# PI_CAN_Interface_v3.net
KiCad netlist of a schematic drawn in Altium Designer
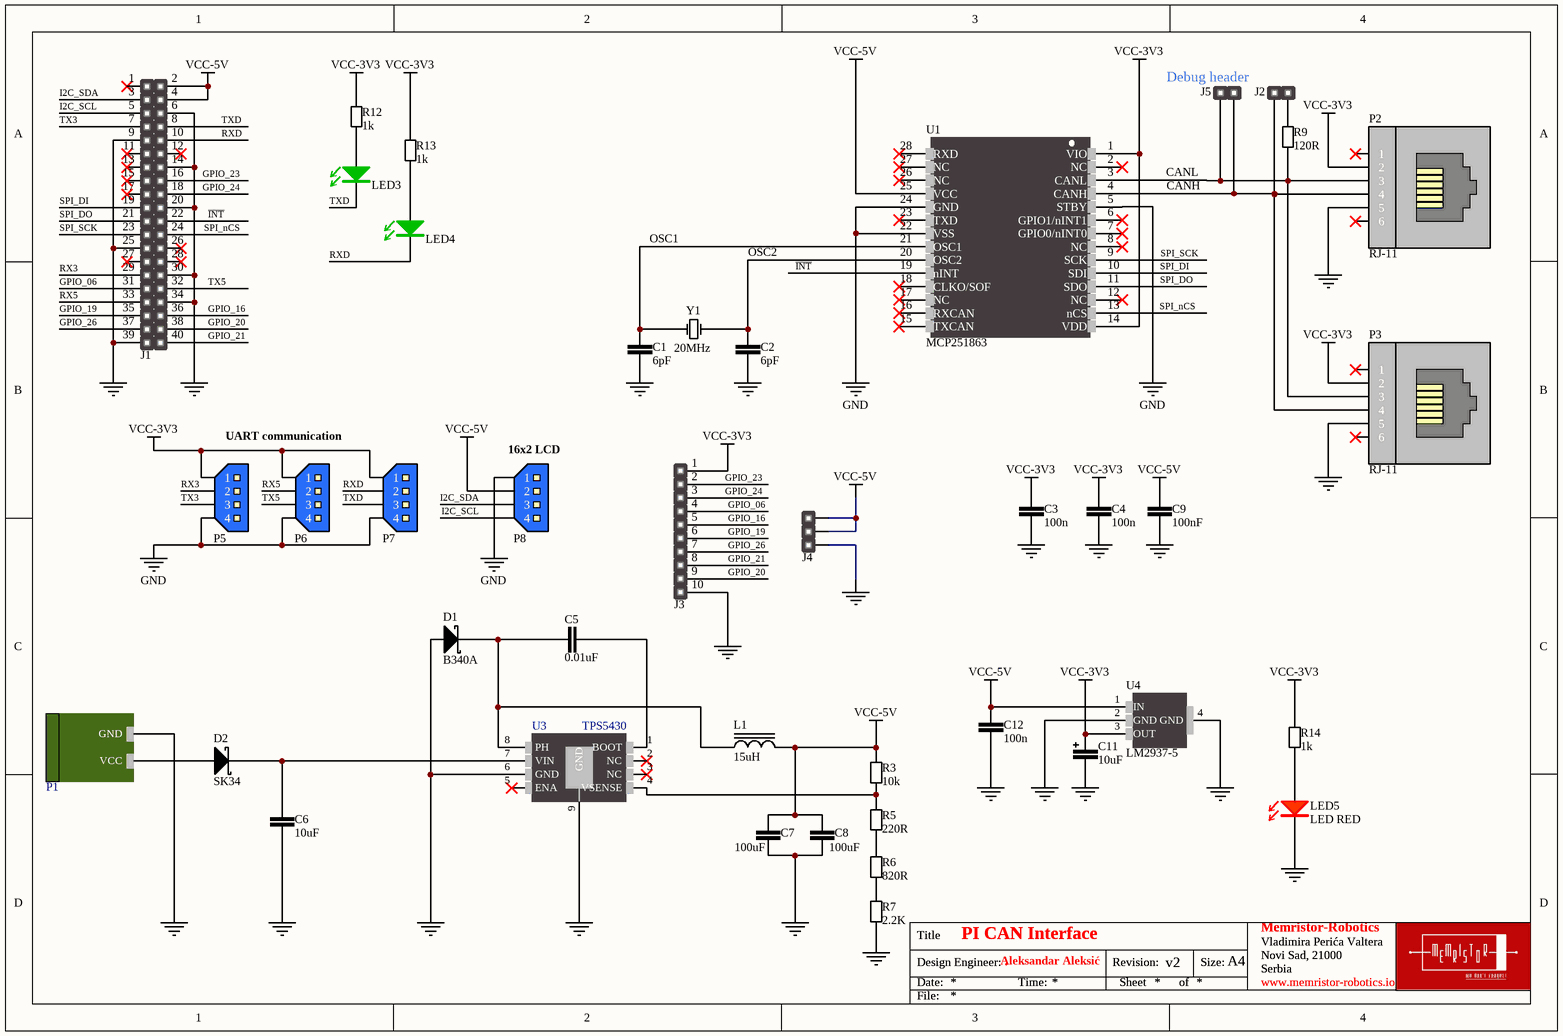
[diagram p0: PI_CAN_Interface_v3.SchDoc]

(export (version "E")
  (design (tool "Eeschema 10.0.6"))
  (components
    (comp (ref "C1")
      (value "6pF")
      (footprint "CER_0603")
      (description "CAP CER 20p 0805")
      (libsource (lib "Capacitors") (part "00002200"))
    )
    (comp (ref "C2")
      (value "6pF")
      (footprint "CER_0603")
      (description "CAP CER 20p 0805")
      (libsource (lib "Capacitors") (part "00002200"))
    )
    (comp (ref "C3")
      (value "100n")
      (footprint "CER_0603")
      (description "CAP CER 100n 10V X5R 10% 0603")
      (libsource (lib "Capacitors") (part "06032105"))
    )
    (comp (ref "C4")
      (value "100n")
      (footprint "CER_0603")
      (description "CAP CER 100n 10V X5R 10% 0603")
      (libsource (lib "Capacitors") (part "06032105"))
    )
    (comp (ref "C5")
      (value "0.01uF")
      (footprint "CER_0603")
      (description "CAP CER 100n 10V X5R 10% 0603")
      (libsource (lib "Capacitors") (part "06032105"))
    )
    (comp (ref "C6")
      (value "10uF")
      (footprint "CER_1210")
      (description "CAP CER 2.2u X7R 100V 20% 1210")
      (libsource (lib "Capacitors") (part "00002225"))
    )
    (comp (ref "C7")
      (value "100uF")
      (footprint "CER_1210")
      (description "CAP CER 100u X5R 6.3V 10% 1210")
      (libsource (lib "Capacitors") (part "00002108"))
    )
    (comp (ref "C8")
      (value "100uF")
      (footprint "CER_1210")
      (description "CAP CER 100u X5R 6.3V 10% 1210")
      (libsource (lib "Capacitors") (part "00002108"))
    )
    (comp (ref "C9")
      (value "100nF")
      (footprint "CER_0805")
      (description "CAP CER 100n 50V X7R 10% 0805")
      (libsource (lib "Capacitors") (part "00002105"))
    )
    (comp (ref "C11")
      (value "10uF")
      (footprint "Capacitors:TANT_1210")
      (description "CAP TANT 10u")
      (libsource (lib "Capacitors") (part "00001106"))
    )
    (comp (ref "C12")
      (value "100n")
      (footprint "CER_0603")
      (description "CAP CER 100n 10V X5R 10% 0603")
      (libsource (lib "Capacitors") (part "06032105"))
    )
    (comp (ref "D1")
      (value "B340A")
      (footprint "DO214AC")
      (description "DIODE SCHOTTKY 60V 3A DO214AC")
      (fields (field (name "MANUFACTURER") "Vishay Semiconductor Diodes Division"))
      (libsource (lib "Discrete_Semiconductor") (part "B360B"))
    )
    (comp (ref "D2")
      (value "SK34")
      (footprint "DO214AC")
      (description "DIODE SCHOTTKY 40V 3A DO214AC")
      (fields (field (name "MANUFACTURER") "Vishay Semiconductor Diodes Division"))
      (libsource (lib "Discrete_Semiconductor") (part "SK34"))
    )
    (comp (ref "J1")
      (value "00000005")
      (footprint "HM2X20")
      (libsource (lib "Electro_Mechanical") (part "00000005"))
    )
    (comp (ref "J2")
      (value "*")
      (footprint "Electro_Mechanical:HM1x2")
      (libsource (lib "Electro_Mechanical") (part "00000003"))
    )
    (comp (ref "J3")
      (value "00000006")
      (footprint "HM1X10")
      (libsource (lib "Electro_Mechanical") (part "00000006"))
    )
    (comp (ref "J4")
      (value "*")
      (footprint "HM1X3")
      (libsource (lib "Electro_Mechanical") (part "HEADER_1x3"))
    )
    (comp (ref "J5")
      (value "*")
      (footprint "HM1x2")
      (libsource (lib "Electro_Mechanical") (part "HEADER_1x2"))
    )
    (comp (ref "L1")
      (value "15uH")
      (footprint "INDUCTOR_SS1260-103MLD")
      (description "FIXED IND 10uH 3A")
      (fields
        (field (name "MANUFACTURER") "Coilcraft")
        (field (name "MANUFACTURER PART NUMBER") "XAL7030-103MEB")
      )
      (libsource (lib "Discrete_Semiconductor") (part "IND_10uH"))
    )
    (comp (ref "LED3")
      (value "LED GREEN")
      (footprint "LED_GREEN_0805")
      (description "LED GREEN CLEAR 0805 SMD")
      (fields
        (field (name "MANUFACTURER") "Kingbright")
        (field (name "MANUFACTURER PART NUMBER") "APT2012SGC")
      )
      (libsource (lib "Discrete_Semiconductor") (part "LED_GREEN 0805"))
    )
    (comp (ref "LED4")
      (value "LED GREEN")
      (footprint "LED_GREEN_0805")
      (description "LED GREEN CLEAR 0805 SMD")
      (fields
        (field (name "MANUFACTURER") "Kingbright")
        (field (name "MANUFACTURER PART NUMBER") "APT2012SGC")
      )
      (libsource (lib "Discrete_Semiconductor") (part "LED_GREEN 0805"))
    )
    (comp (ref "LED5")
      (value "LED RED")
      (footprint "LED_RED_0805")
      (description "LED RED 0805")
      (fields
        (field (name "MANUFACTURER") "BRIGHT LED ELECTRONICS")
        (field (name "MANUFACTURER PART NUMBER") "BL-HUB35A-AV-TRB")
      )
      (libsource (lib "Discrete_Semiconductor") (part "LED_RED_0805"))
    )
    (comp (ref "P1")
      (value "*")
      (footprint "PWR_Con")
      (libsource (lib "Electro_Mechanical") (part "00000002"))
    )
    (comp (ref "P2")
      (value "RJ-11")
      (footprint "RJ11-6N-B")
      (libsource (lib "Electro_Mechanical") (part "00000001"))
    )
    (comp (ref "P3")
      (value "RJ-11")
      (footprint "RJ11-6N-B")
      (libsource (lib "Electro_Mechanical") (part "00000001"))
    )
    (comp (ref "P5")
      (value "TE CONNECTIVITY_4PIN_MALE")
      (footprint "TE CONNECTIVITY_4PIN_MALE")
      (description "BLUE_4PIN_CONECTOR")
      (fields (field (name "MANUFACTURER") "TE CONNECTIVITY / AMP"))
      (libsource (lib "Electro_Mechanical") (part "TE CONNECTIVITY_4PIN_MALE"))
    )
    (comp (ref "P6")
      (value "TE CONNECTIVITY_4PIN_MALE")
      (footprint "TE CONNECTIVITY_4PIN_MALE")
      (description "BLUE_4PIN_CONECTOR")
      (fields (field (name "MANUFACTURER") "TE CONNECTIVITY / AMP"))
      (libsource (lib "Electro_Mechanical") (part "TE CONNECTIVITY_4PIN_MALE"))
    )
    (comp (ref "P7")
      (value "TE CONNECTIVITY_4PIN_MALE")
      (footprint "TE CONNECTIVITY_4PIN_MALE")
      (description "BLUE_4PIN_CONECTOR")
      (fields (field (name "MANUFACTURER") "TE CONNECTIVITY / AMP"))
      (libsource (lib "Electro_Mechanical") (part "TE CONNECTIVITY_4PIN_MALE"))
    )
    (comp (ref "P8")
      (value "TE CONNECTIVITY_4PIN_MALE")
      (footprint "TE CONNECTIVITY_4PIN_MALE")
      (description "BLUE_4PIN_CONECTOR")
      (fields (field (name "MANUFACTURER") "TE CONNECTIVITY / AMP"))
      (libsource (lib "Electro_Mechanical") (part "TE CONNECTIVITY_4PIN_MALE"))
    )
    (comp (ref "R3")
      (value "10k")
      (footprint "RESC2013X38N-0805-NOOVERLAY")
      (description "RES SMD 51 kOhm 1/8W 0805")
      (fields (field (name "POWER") "0.125W, 1/8W"))
      (libsource (lib "Resistors") (part "00005102"))
    )
    (comp (ref "R5")
      (value "220R")
      (footprint "RESC2013X38N-0805-NOOVERLAY")
      (description "RES SMD 9.1 kOhm 1/8W 0805")
      (fields (field (name "POWER") "0.125W, 1/8W"))
      (libsource (lib "Resistors") (part "00009101"))
    )
    (comp (ref "R6")
      (value "820R")
      (footprint "RESC2013X38N-0805-NOOVERLAY")
      (description "RES SMD 9.1 kOhm 1/8W 0805")
      (fields (field (name "POWER") "0.125W, 1/8W"))
      (libsource (lib "Resistors") (part "00009101"))
    )
    (comp (ref "R7")
      (value "2.2K")
      (footprint "RESC2013X38N-0805-NOOVERLAY")
      (description "RES SMD 9.1 kOhm 1/8W 0805")
      (fields (field (name "POWER") "0.125W, 1/8W"))
      (libsource (lib "Resistors") (part "00009101"))
    )
    (comp (ref "R9")
      (value "120R")
      (footprint "Resistors:RESC2013X38N-0805-NOOVERLAY")
      (description "RES SMD 120 Ohm 1/8W 0805")
      (libsource (lib "Resistors") (part "000001200"))
    )
    (comp (ref "R12")
      (value "1k")
      (footprint "Resistors:RESC2013X38N-0805-NOOVERLAY")
      (description "RES SMD 1 kOhm 1/8W 0805")
      (fields (field (name "POWER") "0.125W, 1/8W"))
      (libsource (lib "Resistors") (part "00001001"))
    )
    (comp (ref "R13")
      (value "1k")
      (footprint "Resistors:RESC2013X38N-0805-NOOVERLAY")
      (description "RES SMD 1 kOhm 1/8W 0805")
      (fields (field (name "POWER") "0.125W, 1/8W"))
      (libsource (lib "Resistors") (part "00001001"))
    )
    (comp (ref "R14")
      (value "1k")
      (footprint "Resistors:RESC2013X38N-0805-NOOVERLAY")
      (description "RES SMD 1 kOhm 1/8W 0805")
      (fields (field (name "POWER") "0.125W, 1/8W"))
      (libsource (lib "Resistors") (part "00001001"))
    )
    (comp (ref "U1")
      (value "MCP251863")
      (footprint "SSOP-28")
      (libsource (lib "Integrated_circuits") (part "MCP251863"))
    )
    (comp (ref "U3") (value "TPS5430") (footprint "HSOP-8") (libsource (lib "TPS5430") (part "TPS5430")))
    (comp (ref "U4")
      (value "LM2937-5")
      (footprint "Integrated_circuits:SOT223")
      (description "IC REG LINEAR 5V 400MA SOT223-4")
      (libsource (lib "Integrated_circuits") (part "00000007"))
    )
    (comp (ref "Y1")
      (value "20MHz")
      (footprint "OSCILATOR")
      (description "Crystal Oscillator")
      (fields (field (name "PUBLISHER") "Altium Limited"))
      (libsource (lib "Discrete_Semiconductor") (part "XtalSmd"))
    )
  )
  (nets
    (net (code "1") (name "/CANH") (class "Default")
      (node (ref "J2") (pin "1") (pinfunction "1_1") (pintype "passive"))
      (node (ref "J5") (pin "2") (pinfunction "1_2") (pintype "passive"))
      (node (ref "P2") (pin "4") (pinfunction "4_4") (pintype "passive"))
      (node (ref "P3") (pin "4") (pinfunction "4_4") (pintype "passive"))
      (node (ref "U1") (pin "4") (pinfunction "CANH_4") (pintype "passive"))
    )
    (net (code "2") (name "/CANL") (class "Default")
      (node (ref "J5") (pin "1") (pinfunction "1_1") (pintype "passive"))
      (node (ref "P2") (pin "3") (pinfunction "3_3") (pintype "passive"))
      (node (ref "P3") (pin "3") (pinfunction "3_3") (pintype "passive"))
      (node (ref "R9") (pin "1") (pinfunction "1_1") (pintype "passive"))
      (node (ref "U1") (pin "3") (pinfunction "CANL_3") (pintype "passive"))
    )
    (net (code "3") (name "/GPIO_06") (class "Default")
      (node (ref "J1") (pin "31") (pinfunction "31_31") (pintype "passive"))
      (node (ref "J3") (pin "4") (pinfunction "1_4") (pintype "passive"))
    )
    (net (code "4") (name "/GPIO_16") (class "Default")
      (node (ref "J1") (pin "36") (pinfunction "36_36") (pintype "passive"))
      (node (ref "J3") (pin "5") (pinfunction "1_5") (pintype "passive"))
    )
    (net (code "5") (name "/GPIO_19") (class "Default")
      (node (ref "J1") (pin "35") (pinfunction "35_35") (pintype "passive"))
      (node (ref "J3") (pin "6") (pinfunction "1_6") (pintype "passive"))
    )
    (net (code "6") (name "/GPIO_20") (class "Default")
      (node (ref "J1") (pin "38") (pinfunction "38_38") (pintype "passive"))
      (node (ref "J3") (pin "9") (pinfunction "1_9") (pintype "passive"))
    )
    (net (code "7") (name "/GPIO_21") (class "Default")
      (node (ref "J1") (pin "40") (pinfunction "40_40") (pintype "passive"))
      (node (ref "J3") (pin "8") (pinfunction "1_8") (pintype "passive"))
    )
    (net (code "8") (name "/GPIO_23") (class "Default")
      (node (ref "J1") (pin "16") (pinfunction "16_16") (pintype "passive"))
      (node (ref "J3") (pin "2") (pinfunction "1_2") (pintype "passive"))
    )
    (net (code "9") (name "/GPIO_24") (class "Default")
      (node (ref "J1") (pin "18") (pinfunction "18_18") (pintype "passive"))
      (node (ref "J3") (pin "3") (pinfunction "1_3") (pintype "passive"))
    )
    (net (code "10") (name "/GPIO_26") (class "Default")
      (node (ref "J1") (pin "37") (pinfunction "37_37") (pintype "passive"))
      (node (ref "J3") (pin "7") (pinfunction "1_7") (pintype "passive"))
    )
    (net (code "11") (name "/I2C_SCL") (class "Default")
      (node (ref "J1") (pin "5") (pinfunction "5_5") (pintype "passive"))
      (node (ref "P8") (pin "4") (pinfunction "4_4") (pintype "passive"))
    )
    (net (code "12") (name "/I2C_SDA") (class "Default")
      (node (ref "J1") (pin "3") (pinfunction "3_3") (pintype "passive"))
      (node (ref "P8") (pin "3") (pinfunction "3_3") (pintype "passive"))
    )
    (net (code "13") (name "/OSC1") (class "Default")
      (node (ref "C1") (pin "2") (pinfunction "2_2") (pintype "passive"))
      (node (ref "U1") (pin "21") (pinfunction "OSC1_21") (pintype "passive"))
      (node (ref "Y1") (pin "1") (pinfunction "OSC1_1") (pintype "passive"))
    )
    (net (code "14") (name "/OSC2") (class "Default")
      (node (ref "C2") (pin "2") (pinfunction "2_2") (pintype "passive"))
      (node (ref "U1") (pin "20") (pinfunction "OSC2_20") (pintype "passive"))
      (node (ref "Y1") (pin "2") (pinfunction "OSC2_2") (pintype "passive"))
    )
    (net (code "15") (name "/RX3") (class "Default")
      (node (ref "J1") (pin "29") (pinfunction "29_29") (pintype "passive"))
      (node (ref "P5") (pin "2") (pinfunction "2_2") (pintype "passive"))
    )
    (net (code "16") (name "/RX5") (class "Default")
      (node (ref "J1") (pin "33") (pinfunction "33_33") (pintype "passive"))
      (node (ref "P6") (pin "2") (pinfunction "2_2") (pintype "passive"))
    )
    (net (code "17") (name "/RXD") (class "Default")
      (node (ref "J1") (pin "10") (pinfunction "10_10") (pintype "passive"))
      (node (ref "LED4") (pin "1") (pinfunction "C_1") (pintype "passive"))
      (node (ref "P7") (pin "2") (pinfunction "2_2") (pintype "passive"))
    )
    (net (code "18") (name "/SPI_DI") (class "Default")
      (node (ref "J1") (pin "19") (pinfunction "19_19") (pintype "passive"))
      (node (ref "U1") (pin "10") (pinfunction "SDI_10") (pintype "passive"))
    )
    (net (code "19") (name "/SPI_DO") (class "Default")
      (node (ref "J1") (pin "21") (pinfunction "21_21") (pintype "passive"))
      (node (ref "U1") (pin "11") (pinfunction "SDO_11") (pintype "passive"))
    )
    (net (code "20") (name "/SPI_SCK") (class "Default")
      (node (ref "J1") (pin "23") (pinfunction "23_23") (pintype "passive"))
      (node (ref "U1") (pin "9") (pinfunction "SCK_9") (pintype "passive"))
    )
    (net (code "21") (name "/SPI_nCS") (class "Default")
      (node (ref "J1") (pin "24") (pinfunction "24_24") (pintype "passive"))
      (node (ref "U1") (pin "13") (pinfunction "nCS_13") (pintype "passive"))
    )
    (net (code "22") (name "/TX3") (class "Default")
      (node (ref "J1") (pin "7") (pinfunction "7_7") (pintype "passive"))
      (node (ref "P5") (pin "3") (pinfunction "3_3") (pintype "passive"))
    )
    (net (code "23") (name "/TX5") (class "Default")
      (node (ref "J1") (pin "32") (pinfunction "32_32") (pintype "passive"))
      (node (ref "P6") (pin "3") (pinfunction "3_3") (pintype "passive"))
    )
    (net (code "24") (name "/TXD") (class "Default")
      (node (ref "J1") (pin "8") (pinfunction "8_8") (pintype "passive"))
      (node (ref "LED3") (pin "1") (pinfunction "C_1") (pintype "passive"))
      (node (ref "P7") (pin "3") (pinfunction "3_3") (pintype "passive"))
    )
    (net (code "25") (name "/~{INT}") (class "Default")
      (node (ref "J1") (pin "22") (pinfunction "22_22") (pintype "passive"))
      (node (ref "U1") (pin "19") (pinfunction "nINT_19") (pintype "passive"))
    )
    (net (code "26") (name "GND") (class "Default")
      (node (ref "C1") (pin "1") (pinfunction "1_1") (pintype "passive"))
      (node (ref "C11") (pin "2") (pinfunction "2_2") (pintype "passive"))
      (node (ref "C12") (pin "1") (pinfunction "1_1") (pintype "passive"))
      (node (ref "C2") (pin "1") (pinfunction "1_1") (pintype "passive"))
      (node (ref "C3") (pin "1") (pinfunction "1_1") (pintype "passive"))
      (node (ref "C4") (pin "1") (pinfunction "1_1") (pintype "passive"))
      (node (ref "C6") (pin "1") (pinfunction "1_1") (pintype "passive"))
      (node (ref "C7") (pin "1") (pinfunction "1_1") (pintype "passive"))
      (node (ref "C8") (pin "1") (pinfunction "1_1") (pintype "passive"))
      (node (ref "C9") (pin "1") (pinfunction "1_1") (pintype "passive"))
      (node (ref "D1") (pin "2") (pinfunction "Anode_2") (pintype "passive"))
      (node (ref "J1") (pin "14") (pinfunction "14_14") (pintype "passive"))
      (node (ref "J1") (pin "20") (pinfunction "20_20") (pintype "passive"))
      (node (ref "J1") (pin "25") (pinfunction "25_25") (pintype "passive"))
      (node (ref "J1") (pin "30") (pinfunction "30_30") (pintype "passive"))
      (node (ref "J1") (pin "34") (pinfunction "34_34") (pintype "passive"))
      (node (ref "J1") (pin "39") (pinfunction "39_39") (pintype "passive"))
      (node (ref "J1") (pin "6") (pinfunction "6_6") (pintype "passive"))
      (node (ref "J1") (pin "9") (pinfunction "9_9") (pintype "passive"))
      (node (ref "J3") (pin "10") (pinfunction "1_10") (pintype "passive"))
      (node (ref "J4") (pin "3") (pinfunction "3_3") (pintype "passive"))
      (node (ref "LED5") (pin "1") (pinfunction "C_1") (pintype "passive"))
      (node (ref "P1") (pin "1") (pinfunction "GND_1") (pintype "passive"))
      (node (ref "P2") (pin "5") (pinfunction "5_5") (pintype "passive"))
      (node (ref "P3") (pin "5") (pinfunction "5_5") (pintype "passive"))
      (node (ref "P5") (pin "4") (pinfunction "4_4") (pintype "passive"))
      (node (ref "P6") (pin "4") (pinfunction "4_4") (pintype "passive"))
      (node (ref "P7") (pin "4") (pinfunction "4_4") (pintype "passive"))
      (node (ref "P8") (pin "1") (pinfunction "1_1") (pintype "passive"))
      (node (ref "R7") (pin "1") (pinfunction "1_1") (pintype "passive"))
      (node (ref "U1") (pin "22") (pinfunction "VSS_22") (pintype "passive"))
      (node (ref "U1") (pin "24") (pinfunction "GND_24") (pintype "passive"))
      (node (ref "U1") (pin "5") (pinfunction "STBY_5") (pintype "passive"))
      (node (ref "U3") (pin "6") (pinfunction "GND_6") (pintype "passive"))
      (node (ref "U3") (pin "9") (pinfunction "GND_9") (pintype "passive"))
      (node (ref "U4") (pin "2") (pinfunction "GND_2") (pintype "passive"))
      (node (ref "U4") (pin "4") (pinfunction "GND_4") (pintype "passive"))
    )
    (net (code "27") (name "Net-(D1-Cathode)") (class "Default")
      (node (ref "C5") (pin "1") (pinfunction "1_1") (pintype "passive"))
      (node (ref "D1") (pin "1") (pinfunction "Cathode_1") (pintype "passive"))
      (node (ref "L1") (pin "1") (pinfunction "1_1") (pintype "passive"))
      (node (ref "U3") (pin "8") (pinfunction "PH_8") (pintype "passive"))
    )
    (net (code "28") (name "Net-(D2-Anode)") (class "Default")
      (node (ref "D2") (pin "2") (pinfunction "Anode_2") (pintype "passive"))
      (node (ref "P1") (pin "2") (pinfunction "VCC_2") (pintype "passive"))
    )
    (net (code "29") (name "Net-(D2-Cathode)") (class "Default")
      (node (ref "C6") (pin "2") (pinfunction "2_2") (pintype "passive"))
      (node (ref "D2") (pin "1") (pinfunction "Cathode_1") (pintype "passive"))
      (node (ref "U3") (pin "7") (pinfunction "VIN_7") (pintype "passive"))
    )
    (net (code "30") (name "Net-(J2-1-Pad2)") (class "Default")
      (node (ref "J2") (pin "2") (pinfunction "1_2") (pintype "passive"))
      (node (ref "R9") (pin "2") (pinfunction "2_2") (pintype "passive"))
    )
    (net (code "31") (name "Net-(LED3-A)") (class "Default")
      (node (ref "LED3") (pin "2") (pinfunction "A_2") (pintype "passive"))
      (node (ref "R12") (pin "1") (pinfunction "1_1") (pintype "passive"))
    )
    (net (code "32") (name "Net-(LED4-A)") (class "Default")
      (node (ref "LED4") (pin "2") (pinfunction "A_2") (pintype "passive"))
      (node (ref "R13") (pin "1") (pinfunction "1_1") (pintype "passive"))
    )
    (net (code "33") (name "Net-(LED5-A)") (class "Default")
      (node (ref "LED5") (pin "2") (pinfunction "A_2") (pintype "passive"))
      (node (ref "R14") (pin "1") (pinfunction "1_1") (pintype "passive"))
    )
    (net (code "34") (name "Net-(R5-Pad1)") (class "Default")
      (node (ref "R5") (pin "1") (pinfunction "1_1") (pintype "passive"))
      (node (ref "R6") (pin "2") (pinfunction "2_2") (pintype "passive"))
    )
    (net (code "35") (name "Net-(R6-Pad1)") (class "Default")
      (node (ref "R6") (pin "1") (pinfunction "1_1") (pintype "passive"))
      (node (ref "R7") (pin "2") (pinfunction "2_2") (pintype "passive"))
    )
    (net (code "36") (name "Net-(U3-BOOT)") (class "Default")
      (node (ref "C5") (pin "2") (pinfunction "2_2") (pintype "passive"))
      (node (ref "U3") (pin "1") (pinfunction "BOOT_1") (pintype "passive"))
    )
    (net (code "37") (name "Net-(U3-VSENSE)") (class "Default")
      (node (ref "R3") (pin "1") (pinfunction "1_1") (pintype "passive"))
      (node (ref "R5") (pin "2") (pinfunction "2_2") (pintype "passive"))
      (node (ref "U3") (pin "4") (pinfunction "VSENSE_4") (pintype "passive"))
    )
    (net (code "38") (name "VCC-3V3") (class "Default")
      (node (ref "C11") (pin "1") (pinfunction "1_1") (pintype "passive"))
      (node (ref "C3") (pin "2") (pinfunction "2_2") (pintype "passive"))
      (node (ref "C4") (pin "2") (pinfunction "2_2") (pintype "passive"))
      (node (ref "J3") (pin "1") (pinfunction "1_1") (pintype "passive"))
      (node (ref "P2") (pin "2") (pinfunction "2_2") (pintype "passive"))
      (node (ref "P3") (pin "2") (pinfunction "2_2") (pintype "passive"))
      (node (ref "P5") (pin "1") (pinfunction "1_1") (pintype "passive"))
      (node (ref "P6") (pin "1") (pinfunction "1_1") (pintype "passive"))
      (node (ref "P7") (pin "1") (pinfunction "1_1") (pintype "passive"))
      (node (ref "R12") (pin "2") (pinfunction "2_2") (pintype "passive"))
      (node (ref "R13") (pin "2") (pinfunction "2_2") (pintype "passive"))
      (node (ref "R14") (pin "2") (pinfunction "2_2") (pintype "passive"))
      (node (ref "U1") (pin "1") (pinfunction "VIO_1") (pintype "passive"))
      (node (ref "U1") (pin "14") (pinfunction "VDD_14") (pintype "passive"))
      (node (ref "U4") (pin "3") (pinfunction "OUT_3") (pintype "passive"))
    )
    (net (code "39") (name "VCC-5V") (class "Default")
      (node (ref "C12") (pin "2") (pinfunction "2_2") (pintype "passive"))
      (node (ref "C7") (pin "2") (pinfunction "2_2") (pintype "passive"))
      (node (ref "C8") (pin "2") (pinfunction "2_2") (pintype "passive"))
      (node (ref "C9") (pin "2") (pinfunction "2_2") (pintype "passive"))
      (node (ref "J1") (pin "2") (pinfunction "2_2") (pintype "passive"))
      (node (ref "J1") (pin "4") (pinfunction "4_4") (pintype "passive"))
      (node (ref "J4") (pin "1") (pinfunction "1_1") (pintype "passive"))
      (node (ref "J4") (pin "2") (pinfunction "2_2") (pintype "passive"))
      (node (ref "L1") (pin "2") (pinfunction "2_2") (pintype "passive"))
      (node (ref "P8") (pin "2") (pinfunction "2_2") (pintype "passive"))
      (node (ref "R3") (pin "2") (pinfunction "2_2") (pintype "passive"))
      (node (ref "U1") (pin "25") (pinfunction "VCC_25") (pintype "passive"))
      (node (ref "U4") (pin "1") (pinfunction "IN_1") (pintype "passive"))
    )
    (net (code "40") (name "unconnected-(J1-Pad1)") (class "Default")
      (node (ref "J1") (pin "1") (pinfunction "1_1") (pintype "passive+no_connect"))
    )
    (net (code "41") (name "unconnected-(J1-Pad11)") (class "Default")
      (node (ref "J1") (pin "11") (pinfunction "11_11") (pintype "passive+no_connect"))
    )
    (net (code "42") (name "unconnected-(J1-Pad12)") (class "Default")
      (node (ref "J1") (pin "12") (pinfunction "12_12") (pintype "passive+no_connect"))
    )
    (net (code "43") (name "unconnected-(J1-Pad13)") (class "Default")
      (node (ref "J1") (pin "13") (pinfunction "13_13") (pintype "passive+no_connect"))
    )
    (net (code "44") (name "unconnected-(J1-Pad15)") (class "Default")
      (node (ref "J1") (pin "15") (pinfunction "15_15") (pintype "passive+no_connect"))
    )
    (net (code "45") (name "unconnected-(J1-Pad17)") (class "Default")
      (node (ref "J1") (pin "17") (pinfunction "17_17") (pintype "passive+no_connect"))
    )
    (net (code "46") (name "unconnected-(J1-Pad26)") (class "Default")
      (node (ref "J1") (pin "26") (pinfunction "26_26") (pintype "passive+no_connect"))
    )
    (net (code "47") (name "unconnected-(J1-Pad27)") (class "Default")
      (node (ref "J1") (pin "27") (pinfunction "27_27") (pintype "passive+no_connect"))
    )
    (net (code "48") (name "unconnected-(J1-Pad28)") (class "Default")
      (node (ref "J1") (pin "28") (pinfunction "28_28") (pintype "passive+no_connect"))
    )
    (net (code "49") (name "unconnected-(P2-Pad1)") (class "Default")
      (node (ref "P2") (pin "1") (pinfunction "1_1") (pintype "passive+no_connect"))
    )
    (net (code "50") (name "unconnected-(P2-Pad6)") (class "Default")
      (node (ref "P2") (pin "6") (pinfunction "6_6") (pintype "passive+no_connect"))
    )
    (net (code "51") (name "unconnected-(P3-Pad1)") (class "Default")
      (node (ref "P3") (pin "1") (pinfunction "1_1") (pintype "passive+no_connect"))
    )
    (net (code "52") (name "unconnected-(P3-Pad6)") (class "Default")
      (node (ref "P3") (pin "6") (pinfunction "6_6") (pintype "passive+no_connect"))
    )
    (net (code "53") (name "unconnected-(U1-CLKO{slash}SOF-Pad18)") (class "Default")
      (node (ref "U1") (pin "18") (pinfunction "CLKO/SOF_18") (pintype "passive+no_connect"))
    )
    (net (code "54") (name "unconnected-(U1-GPIO0{slash}nINT0-Pad7)") (class "Default")
      (node (ref "U1") (pin "7") (pinfunction "GPIO0/nINT0_7") (pintype "passive+no_connect"))
    )
    (net (code "55") (name "unconnected-(U1-GPIO1{slash}nINT1-Pad6)") (class "Default")
      (node (ref "U1") (pin "6") (pinfunction "GPIO1/nINT1_6") (pintype "passive+no_connect"))
    )
    (net (code "56") (name "unconnected-(U1-NC-Pad2)") (class "Default")
      (node (ref "U1") (pin "2") (pinfunction "NC_2") (pintype "passive+no_connect"))
    )
    (net (code "57") (name "unconnected-(U1-NC-Pad8)") (class "Default")
      (node (ref "U1") (pin "8") (pinfunction "NC_8") (pintype "passive+no_connect"))
    )
    (net (code "58") (name "unconnected-(U1-NC-Pad12)") (class "Default")
      (node (ref "U1") (pin "12") (pinfunction "NC_12") (pintype "passive+no_connect"))
    )
    (net (code "59") (name "unconnected-(U1-NC-Pad17)") (class "Default")
      (node (ref "U1") (pin "17") (pinfunction "NC_17") (pintype "passive+no_connect"))
    )
    (net (code "60") (name "unconnected-(U1-NC-Pad26)") (class "Default")
      (node (ref "U1") (pin "26") (pinfunction "NC_26") (pintype "passive+no_connect"))
    )
    (net (code "61") (name "unconnected-(U1-NC-Pad27)") (class "Default")
      (node (ref "U1") (pin "27") (pinfunction "NC_27") (pintype "passive+no_connect"))
    )
    (net (code "62") (name "unconnected-(U1-RXCAN-Pad16)") (class "Default")
      (node (ref "U1") (pin "16") (pinfunction "RXCAN_16") (pintype "passive+no_connect"))
    )
    (net (code "63") (name "unconnected-(U1-RXD-Pad28)") (class "Default")
      (node (ref "U1") (pin "28") (pinfunction "RXD_28") (pintype "passive+no_connect"))
    )
    (net (code "64") (name "unconnected-(U1-TXCAN-Pad15)") (class "Default")
      (node (ref "U1") (pin "15") (pinfunction "TXCAN_15") (pintype "passive+no_connect"))
    )
    (net (code "65") (name "unconnected-(U1-TXD-Pad23)") (class "Default")
      (node (ref "U1") (pin "23") (pinfunction "TXD_23") (pintype "passive+no_connect"))
    )
    (net (code "66") (name "unconnected-(U3-ENA-Pad5)") (class "Default")
      (node (ref "U3") (pin "5") (pinfunction "ENA_5") (pintype "passive+no_connect"))
    )
    (net (code "67") (name "unconnected-(U3-NC-Pad2)") (class "Default")
      (node (ref "U3") (pin "2") (pinfunction "NC_2") (pintype "passive+no_connect"))
    )
    (net (code "68") (name "unconnected-(U3-NC-Pad3)") (class "Default")
      (node (ref "U3") (pin "3") (pinfunction "NC_3") (pintype "passive+no_connect"))
    )
  )
)
